# Top_Level.net
KiCad netlist of a schematic drawn in Altium Designer
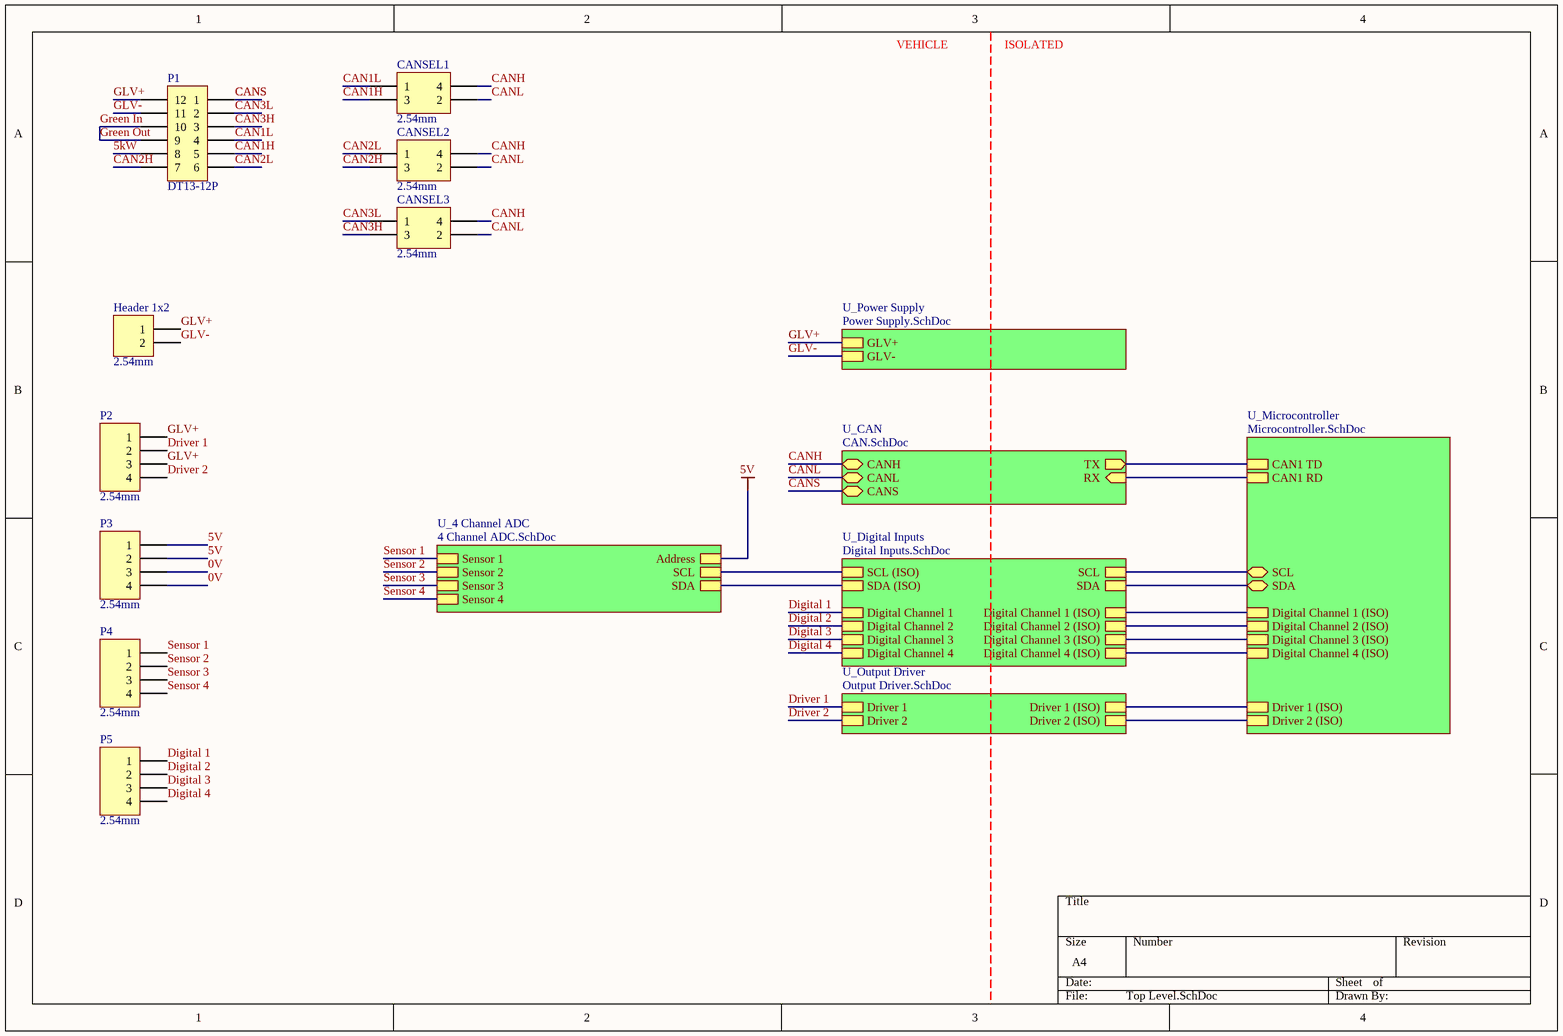
[diagram p0: Top Level.SchDoc]

(export (version "E")
  (design (tool "Eeschema 10.0.6"))
  (components
    (comp (ref "CANSEL1")
      (value "2.54mm")
      (footprint "TH 2.54mm Header 2x2")
      (fields (field (name "PART NUMBER") "TH 2.54mm Header 2x2") (field (name "CONTACT") "NA"))
      (libsource (lib "ts_20-standard-connectors") (part "Header 2x2"))
    )
    (comp (ref "CANSEL2")
      (value "2.54mm")
      (footprint "TH 2.54mm Header 2x2")
      (fields (field (name "PART NUMBER") "TH 2.54mm Header 2x2") (field (name "CONTACT") "NA"))
      (libsource (lib "ts_20-standard-connectors") (part "Header 2x2"))
    )
    (comp (ref "CANSEL3")
      (value "2.54mm")
      (footprint "TH 2.54mm Header 2x2")
      (fields (field (name "PART NUMBER") "TH 2.54mm Header 2x2") (field (name "CONTACT") "NA"))
      (libsource (lib "ts_20-standard-connectors") (part "Header 2x2"))
    )
    (comp (ref "Header 1x2")
      (value "2.54mm")
      (footprint "TH 5.08mm Header 1x2")
      (fields (field (name "PART NUMBER") "TH 5.08mm Header 1x2") (field (name "CONTACT") "NA"))
      (libsource (lib "ts_20-standard-connectors") (part "Header 1x2"))
    )
    (comp (ref "P1")
      (value "DT13-12P")
      (footprint "DT13-12P")
      (fields (field (name "DIGIKEY PART NUMBER") "1734-1451-ND") (field (name "CONTACT") "Nickel"))
      (libsource (lib "ts_20-standard-connectors") (part "DT13-12P"))
    )
    (comp (ref "P2")
      (value "2.54mm")
      (footprint "TH 5.08mm Header 1x4")
      (fields (field (name "PART NUMBER") "TH 5.08mm Header 1x4") (field (name "CONTACT") "NA"))
      (libsource (lib "ts_20-standard-connectors") (part "Header 1x4"))
    )
    (comp (ref "P3")
      (value "2.54mm")
      (footprint "TH 5.08mm Header 1x4")
      (fields (field (name "PART NUMBER") "TH 5.08mm Header 1x4") (field (name "CONTACT") "NA"))
      (libsource (lib "ts_20-standard-connectors") (part "Header 1x4"))
    )
    (comp (ref "P4")
      (value "2.54mm")
      (footprint "TH 5.08mm Header 1x4")
      (fields (field (name "PART NUMBER") "TH 5.08mm Header 1x4") (field (name "CONTACT") "NA"))
      (libsource (lib "ts_20-standard-connectors") (part "Header 1x4"))
    )
    (comp (ref "P5")
      (value "2.54mm")
      (footprint "TH 5.08mm Header 1x4")
      (fields (field (name "PART NUMBER") "TH 5.08mm Header 1x4") (field (name "CONTACT") "NA"))
      (libsource (lib "ts_20-standard-connectors") (part "Header 1x4"))
    )
  )
  (nets
    (net (code "1") (name "/0V") (class "Default")
      (node (ref "P3") (pin "3") (pinfunction "3_3") (pintype "passive"))
      (node (ref "P3") (pin "4") (pinfunction "4_4") (pintype "passive"))
    )
    (net (code "2") (name "/5kW") (class "Default")
      (node (ref "P1") (pin "8") (pinfunction "8_8") (pintype "passive"))
    )
    (net (code "4") (name "/CAN1H") (class "Default")
      (node (ref "CANSEL1") (pin "3") (pinfunction "3_3") (pintype "passive"))
      (node (ref "P1") (pin "5") (pinfunction "5_5") (pintype "power_in"))
    )
    (net (code "5") (name "/CAN1L") (class "Default")
      (node (ref "CANSEL1") (pin "1") (pinfunction "1_1") (pintype "passive"))
      (node (ref "P1") (pin "4") (pinfunction "4_4") (pintype "power_in"))
    )
    (net (code "6") (name "/CAN2H") (class "Default")
      (node (ref "CANSEL2") (pin "3") (pinfunction "3_3") (pintype "passive"))
      (node (ref "P1") (pin "7") (pinfunction "7_7") (pintype "passive"))
    )
    (net (code "7") (name "/CAN2L") (class "Default")
      (node (ref "CANSEL2") (pin "1") (pinfunction "1_1") (pintype "passive"))
      (node (ref "P1") (pin "6") (pinfunction "6_6") (pintype "power_in"))
    )
    (net (code "8") (name "/CAN3H") (class "Default")
      (node (ref "CANSEL3") (pin "3") (pinfunction "3_3") (pintype "passive"))
      (node (ref "P1") (pin "3") (pinfunction "3_3") (pintype "power_in"))
    )
    (net (code "9") (name "/CAN3L") (class "Default")
      (node (ref "CANSEL3") (pin "1") (pinfunction "1_1") (pintype "passive"))
      (node (ref "P1") (pin "2") (pinfunction "2_2") (pintype "power_in"))
    )
    (net (code "10") (name "/CANH") (class "Default")
      (node (ref "CANSEL1") (pin "4") (pinfunction "4_4") (pintype "passive"))
      (node (ref "CANSEL2") (pin "4") (pinfunction "4_4") (pintype "passive"))
      (node (ref "CANSEL3") (pin "4") (pinfunction "4_4") (pintype "passive"))
    )
    (net (code "11") (name "/CANL") (class "Default")
      (node (ref "CANSEL1") (pin "2") (pinfunction "2_2") (pintype "passive"))
      (node (ref "CANSEL2") (pin "2") (pinfunction "2_2") (pintype "passive"))
      (node (ref "CANSEL3") (pin "2") (pinfunction "2_2") (pintype "passive"))
    )
    (net (code "12") (name "/CANS") (class "Default")
      (node (ref "P1") (pin "1") (pinfunction "1_1") (pintype "power_in"))
    )
    (net (code "13") (name "/Digital 1") (class "Default")
      (node (ref "P5") (pin "1") (pinfunction "1_1") (pintype "passive"))
    )
    (net (code "14") (name "/Digital 2") (class "Default")
      (node (ref "P5") (pin "2") (pinfunction "2_2") (pintype "passive"))
    )
    (net (code "15") (name "/Digital 3") (class "Default")
      (node (ref "P5") (pin "3") (pinfunction "3_3") (pintype "passive"))
    )
    (net (code "16") (name "/Digital 4") (class "Default")
      (node (ref "P5") (pin "4") (pinfunction "4_4") (pintype "passive"))
    )
    (net (code "21") (name "/Driver 1") (class "Default")
      (node (ref "P2") (pin "2") (pinfunction "2_2") (pintype "passive"))
    )
    (net (code "23") (name "/Driver 2") (class "Default")
      (node (ref "P2") (pin "4") (pinfunction "4_4") (pintype "passive"))
    )
    (net (code "25") (name "/GLV+") (class "Default")
      (node (ref "Header 1x2") (pin "1") (pinfunction "1_1") (pintype "passive"))
      (node (ref "P1") (pin "12") (pinfunction "12_12") (pintype "passive"))
      (node (ref "P2") (pin "1") (pinfunction "1_1") (pintype "passive"))
      (node (ref "P2") (pin "3") (pinfunction "3_3") (pintype "passive"))
    )
    (net (code "26") (name "/GLV-") (class "Default")
      (node (ref "Header 1x2") (pin "2") (pinfunction "2_2") (pintype "passive"))
      (node (ref "P1") (pin "11") (pinfunction "11_11") (pintype "passive"))
    )
    (net (code "27") (name "/Green In") (class "Default")
      (node (ref "P1") (pin "10") (pinfunction "10_10") (pintype "passive"))
      (node (ref "P1") (pin "9") (pinfunction "9_9") (pintype "passive"))
    )
    (net (code "32") (name "/Sensor 1") (class "Default")
      (node (ref "P4") (pin "1") (pinfunction "1_1") (pintype "passive"))
    )
    (net (code "33") (name "/Sensor 2") (class "Default")
      (node (ref "P4") (pin "2") (pinfunction "2_2") (pintype "passive"))
    )
    (net (code "34") (name "/Sensor 3") (class "Default")
      (node (ref "P4") (pin "3") (pinfunction "3_3") (pintype "passive"))
    )
    (net (code "35") (name "/Sensor 4") (class "Default")
      (node (ref "P4") (pin "4") (pinfunction "4_4") (pintype "passive"))
    )
    (net (code "37") (name "5V") (class "Default")
      (node (ref "P3") (pin "1") (pinfunction "1_1") (pintype "passive"))
      (node (ref "P3") (pin "2") (pinfunction "2_2") (pintype "passive"))
    )
  )
)
